# Gates.net
KiCad netlist of a schematic drawn in Altium Designer
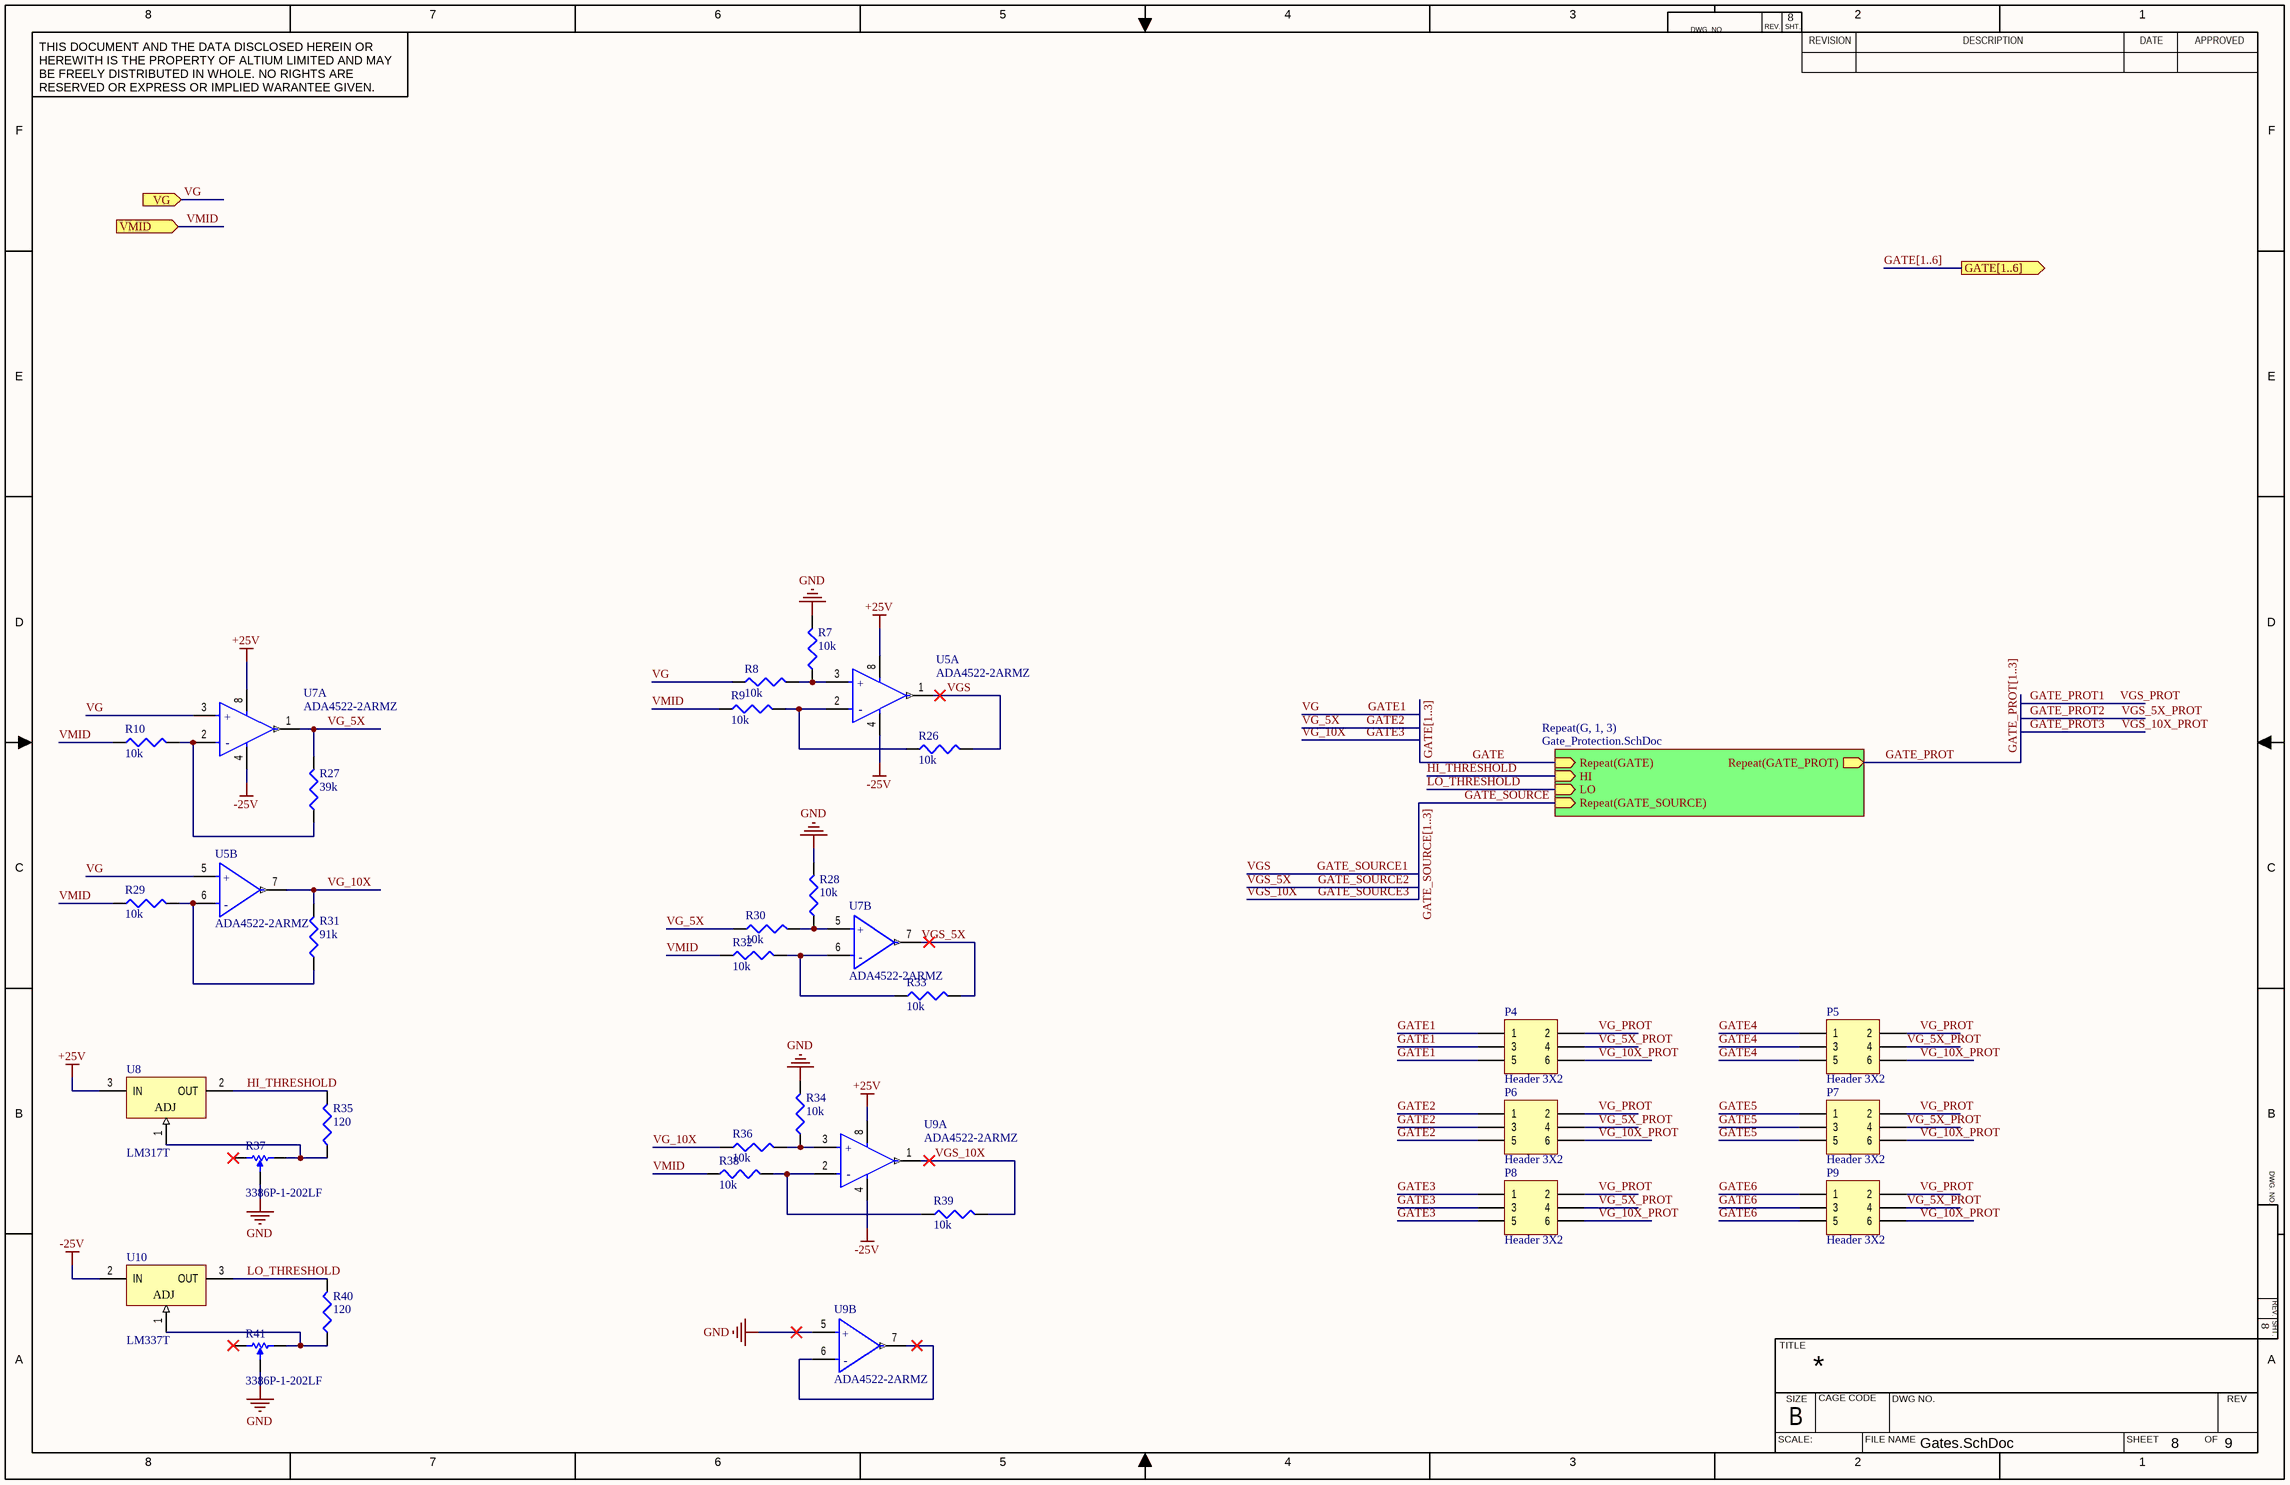
[diagram p0: Gates.SchDoc]

(export (version "E")
  (design (tool "Eeschema 10.0.6"))
  (components
    (comp (ref "P4")
      (value "Header 3X2")
      (footprint "HDR2X3")
      (description "Header, 3-Pin, Dual row")
      (fields (field (name "PUBLISHER") "Altium Limited"))
      (libsource (lib "Miscellaneous Connectors") (part "Header 3X2"))
    )
    (comp (ref "P5")
      (value "Header 3X2")
      (footprint "HDR2X3")
      (description "Header, 3-Pin, Dual row")
      (fields (field (name "PUBLISHER") "Altium Limited"))
      (libsource (lib "Miscellaneous Connectors") (part "Header 3X2"))
    )
    (comp (ref "P6")
      (value "Header 3X2")
      (footprint "HDR2X3")
      (description "Header, 3-Pin, Dual row")
      (fields (field (name "PUBLISHER") "Altium Limited"))
      (libsource (lib "Miscellaneous Connectors") (part "Header 3X2"))
    )
    (comp (ref "P7")
      (value "Header 3X2")
      (footprint "HDR2X3")
      (description "Header, 3-Pin, Dual row")
      (fields (field (name "PUBLISHER") "Altium Limited"))
      (libsource (lib "Miscellaneous Connectors") (part "Header 3X2"))
    )
    (comp (ref "P8")
      (value "Header 3X2")
      (footprint "HDR2X3")
      (description "Header, 3-Pin, Dual row")
      (fields (field (name "PUBLISHER") "Altium Limited"))
      (libsource (lib "Miscellaneous Connectors") (part "Header 3X2"))
    )
    (comp (ref "P9")
      (value "Header 3X2")
      (footprint "HDR2X3")
      (description "Header, 3-Pin, Dual row")
      (fields (field (name "PUBLISHER") "Altium Limited"))
      (libsource (lib "Miscellaneous Connectors") (part "Header 3X2"))
    )
    (comp (ref "R7")
      (value "10k")
      (footprint "J1-0603")
      (description "Resistor")
      (fields (field (name "PUBLISHER") "Altium Limited"))
      (libsource (lib "Miscellaneous Devices") (part "Res3"))
    )
    (comp (ref "R8")
      (value "10k")
      (footprint "J1-0603")
      (description "Resistor")
      (fields (field (name "PUBLISHER") "Altium Limited"))
      (libsource (lib "Miscellaneous Devices") (part "Res3"))
    )
    (comp (ref "R9")
      (value "10k")
      (footprint "J1-0603")
      (description "Resistor")
      (fields (field (name "PUBLISHER") "Altium Limited"))
      (libsource (lib "Miscellaneous Devices") (part "Res3"))
    )
    (comp (ref "R10")
      (value "10k")
      (footprint "J1-0603")
      (description "Resistor")
      (fields (field (name "PUBLISHER") "Altium Limited"))
      (libsource (lib "Miscellaneous Devices") (part "Res3"))
    )
    (comp (ref "R26")
      (value "10k")
      (footprint "J1-0603")
      (description "Resistor")
      (fields (field (name "PUBLISHER") "Altium Limited"))
      (libsource (lib "Miscellaneous Devices") (part "Res3"))
    )
    (comp (ref "R27")
      (value "39k")
      (footprint "J1-0603")
      (description "Resistor")
      (fields (field (name "PUBLISHER") "Altium Limited"))
      (libsource (lib "Miscellaneous Devices") (part "Res3"))
    )
    (comp (ref "R28")
      (value "10k")
      (footprint "J1-0603")
      (description "Resistor")
      (fields (field (name "PUBLISHER") "Altium Limited"))
      (libsource (lib "Miscellaneous Devices") (part "Res3"))
    )
    (comp (ref "R29")
      (value "10k")
      (footprint "J1-0603")
      (description "Resistor")
      (fields (field (name "PUBLISHER") "Altium Limited"))
      (libsource (lib "Miscellaneous Devices") (part "Res3"))
    )
    (comp (ref "R30")
      (value "10k")
      (footprint "J1-0603")
      (description "Resistor")
      (fields (field (name "PUBLISHER") "Altium Limited"))
      (libsource (lib "Miscellaneous Devices") (part "Res3"))
    )
    (comp (ref "R31")
      (value "91k")
      (footprint "J1-0603")
      (description "Resistor")
      (fields (field (name "PUBLISHER") "Altium Limited"))
      (libsource (lib "Miscellaneous Devices") (part "Res3"))
    )
    (comp (ref "R32")
      (value "10k")
      (footprint "J1-0603")
      (description "Resistor")
      (fields (field (name "PUBLISHER") "Altium Limited"))
      (libsource (lib "Miscellaneous Devices") (part "Res3"))
    )
    (comp (ref "R33")
      (value "10k")
      (footprint "J1-0603")
      (description "Resistor")
      (fields (field (name "PUBLISHER") "Altium Limited"))
      (libsource (lib "Miscellaneous Devices") (part "Res3"))
    )
    (comp (ref "R34")
      (value "10k")
      (footprint "J1-0603")
      (description "Resistor")
      (fields (field (name "PUBLISHER") "Altium Limited"))
      (libsource (lib "Miscellaneous Devices") (part "Res3"))
    )
    (comp (ref "R35")
      (value "120")
      (footprint "J1-0603")
      (description "Resistor")
      (fields (field (name "PUBLISHER") "Altium Limited"))
      (libsource (lib "Miscellaneous Devices") (part "Res3"))
    )
    (comp (ref "R36")
      (value "10k")
      (footprint "J1-0603")
      (description "Resistor")
      (fields (field (name "PUBLISHER") "Altium Limited"))
      (libsource (lib "Miscellaneous Devices") (part "Res3"))
    )
    (comp (ref "R37")
      (value "3386P-1-202LF")
      (footprint "BOUR-3386P")
      (fields (field (name "TOLERANCE") "10%") (field (name "MANUFACTURER") "Bourns"))
      (libsource (lib "Altium Content Vault") (part "RES-ADJ-3_A"))
    )
    (comp (ref "R38")
      (value "10k")
      (footprint "J1-0603")
      (description "Resistor")
      (fields (field (name "PUBLISHER") "Altium Limited"))
      (libsource (lib "Miscellaneous Devices") (part "Res3"))
    )
    (comp (ref "R39")
      (value "10k")
      (footprint "J1-0603")
      (description "Resistor")
      (fields (field (name "PUBLISHER") "Altium Limited"))
      (libsource (lib "Miscellaneous Devices") (part "Res3"))
    )
    (comp (ref "R40")
      (value "120")
      (footprint "J1-0603")
      (description "Resistor")
      (fields (field (name "PUBLISHER") "Altium Limited"))
      (libsource (lib "Miscellaneous Devices") (part "Res3"))
    )
    (comp (ref "R41")
      (value "3386P-1-202LF")
      (footprint "BOUR-3386P")
      (fields (field (name "TOLERANCE") "10%") (field (name "MANUFACTURER") "Bourns"))
      (libsource (lib "Altium Content Vault") (part "RES-ADJ-3_A"))
    )
    (comp (ref "U5")
      (value "ADA4522-2ARMZ")
      (footprint "FP-RM-8-IPC_C")
      (description "IC OPAMP ZERO-DRIFT 2 CIRC 8MSOP")
      (libsource (lib "Altium Content Vault") (part "e8c52d48d03680a0ba04c611cf3b55d"))
    )
    (comp (ref "U7")
      (value "ADA4522-2ARMZ")
      (footprint "FP-RM-8-IPC_C")
      (description "IC OPAMP ZERO-DRIFT 2 CIRC 8MSOP")
      (libsource (lib "Altium Content Vault") (part "e8c52d48d03680a0ba04c611cf3b55d"))
    )
    (comp (ref "U8")
      (value "LM317T")
      (footprint "TO-220")
      (description "1.5A, 1.2V to 37V Adjustable Voltage Regulator, 3-Pin TO-220")
      (libsource (lib "Altium Content Vault") (part "PM-REG-117-SIL3"))
    )
    (comp (ref "U9")
      (value "ADA4522-2ARMZ")
      (footprint "FP-RM-8-IPC_C")
      (description "IC OPAMP ZERO-DRIFT 2 CIRC 8MSOP")
      (libsource (lib "Altium Content Vault") (part "e8c52d48d03680a0ba04c611cf3b55d"))
    )
    (comp (ref "U10")
      (value "LM337T")
      (footprint "NDE0003A")
      (description "3-Terminal Adjustable Negative Regulator, 3-pin TO-220")
      (fields (field (name "MANUFACTURER") "Texas Instruments"))
      (libsource (lib "Altium Content Vault") (part "PM-REG-LM150ADJ-CY3"))
    )
  )
  (nets
    (net (code "1") (name "+25V") (class "Default")
      (node (ref "U5") (pin "8") (pinfunction "V+_8") (pintype "power_in"))
      (node (ref "U7") (pin "8") (pinfunction "V+_8") (pintype "power_in"))
      (node (ref "U8") (pin "3") (pinfunction "IN_3") (pintype "power_in"))
      (node (ref "U9") (pin "8") (pinfunction "V+_8") (pintype "power_in"))
    )
    (net (code "2") (name "-25V") (class "Default")
      (node (ref "U10") (pin "2") (pinfunction "IN_2") (pintype "power_in"))
      (node (ref "U5") (pin "4") (pinfunction "V-_4") (pintype "power_in"))
      (node (ref "U7") (pin "4") (pinfunction "V-_4") (pintype "power_in"))
      (node (ref "U9") (pin "4") (pinfunction "V-_4") (pintype "power_in"))
    )
    (net (code "4") (name "/GATE1") (class "Default")
      (node (ref "P4") (pin "1") (pinfunction "1_1") (pintype "passive"))
      (node (ref "P4") (pin "3") (pinfunction "3_3") (pintype "passive"))
      (node (ref "P4") (pin "5") (pinfunction "5_5") (pintype "passive"))
      (node (ref "R8") (pin "1") (pinfunction "1_1") (pintype "passive"))
      (node (ref "U5") (pin "5") (pinfunction "+IN_B_5") (pintype "tri_state"))
      (node (ref "U7") (pin "3") (pinfunction "+IN_A_3") (pintype "tri_state"))
    )
    (net (code "5") (name "/GATE2") (class "Default")
      (node (ref "P6") (pin "1") (pinfunction "1_1") (pintype "passive"))
      (node (ref "P6") (pin "3") (pinfunction "3_3") (pintype "passive"))
      (node (ref "P6") (pin "5") (pinfunction "5_5") (pintype "passive"))
      (node (ref "R27") (pin "2") (pinfunction "2_2") (pintype "passive"))
      (node (ref "R30") (pin "1") (pinfunction "1_1") (pintype "passive"))
      (node (ref "U7") (pin "1") (pinfunction "OUT_A_1") (pintype "output"))
    )
    (net (code "6") (name "/GATE3") (class "Default")
      (node (ref "P8") (pin "1") (pinfunction "1_1") (pintype "passive"))
      (node (ref "P8") (pin "3") (pinfunction "3_3") (pintype "passive"))
      (node (ref "P8") (pin "5") (pinfunction "5_5") (pintype "passive"))
      (node (ref "R31") (pin "2") (pinfunction "2_2") (pintype "passive"))
      (node (ref "R36") (pin "1") (pinfunction "1_1") (pintype "passive"))
      (node (ref "U5") (pin "7") (pinfunction "OUT_B_7") (pintype "output"))
    )
    (net (code "7") (name "/GATE4") (class "Default")
      (node (ref "P5") (pin "1") (pinfunction "1_1") (pintype "passive"))
      (node (ref "P5") (pin "3") (pinfunction "3_3") (pintype "passive"))
      (node (ref "P5") (pin "5") (pinfunction "5_5") (pintype "passive"))
    )
    (net (code "8") (name "/GATE5") (class "Default")
      (node (ref "P7") (pin "1") (pinfunction "1_1") (pintype "passive"))
      (node (ref "P7") (pin "3") (pinfunction "3_3") (pintype "passive"))
      (node (ref "P7") (pin "5") (pinfunction "5_5") (pintype "passive"))
    )
    (net (code "9") (name "/GATE6") (class "Default")
      (node (ref "P9") (pin "1") (pinfunction "1_1") (pintype "passive"))
      (node (ref "P9") (pin "3") (pinfunction "3_3") (pintype "passive"))
      (node (ref "P9") (pin "5") (pinfunction "5_5") (pintype "passive"))
    )
    (net (code "18") (name "/GATE_SOURCE1") (class "Default")
      (node (ref "R26") (pin "2") (pinfunction "2_2") (pintype "passive"))
      (node (ref "U5") (pin "1") (pinfunction "OUT_A_1") (pintype "output"))
    )
    (net (code "19") (name "/GATE_SOURCE2") (class "Default")
      (node (ref "R33") (pin "2") (pinfunction "2_2") (pintype "passive"))
      (node (ref "U7") (pin "7") (pinfunction "OUT_B_7") (pintype "output"))
    )
    (net (code "20") (name "/GATE_SOURCE3") (class "Default")
      (node (ref "R39") (pin "2") (pinfunction "2_2") (pintype "passive"))
      (node (ref "U9") (pin "1") (pinfunction "OUT_A_1") (pintype "output"))
    )
    (net (code "22") (name "/HI_THRESHOLD") (class "Default")
      (node (ref "R35") (pin "2") (pinfunction "2_2") (pintype "passive"))
      (node (ref "U8") (pin "2") (pinfunction "OUT_2") (pintype "power_in"))
    )
    (net (code "23") (name "/LO_THRESHOLD") (class "Default")
      (node (ref "R40") (pin "2") (pinfunction "2_2") (pintype "passive"))
      (node (ref "U10") (pin "3") (pinfunction "OUT_3") (pintype "power_in"))
    )
    (net (code "24") (name "/VG_5X_PROT") (class "Default")
      (node (ref "P4") (pin "4") (pinfunction "4_4") (pintype "passive"))
      (node (ref "P5") (pin "4") (pinfunction "4_4") (pintype "passive"))
      (node (ref "P6") (pin "4") (pinfunction "4_4") (pintype "passive"))
      (node (ref "P7") (pin "4") (pinfunction "4_4") (pintype "passive"))
      (node (ref "P8") (pin "4") (pinfunction "4_4") (pintype "passive"))
      (node (ref "P9") (pin "4") (pinfunction "4_4") (pintype "passive"))
    )
    (net (code "25") (name "/VG_10X_PROT") (class "Default")
      (node (ref "P4") (pin "6") (pinfunction "6_6") (pintype "passive"))
      (node (ref "P5") (pin "6") (pinfunction "6_6") (pintype "passive"))
      (node (ref "P6") (pin "6") (pinfunction "6_6") (pintype "passive"))
      (node (ref "P7") (pin "6") (pinfunction "6_6") (pintype "passive"))
      (node (ref "P8") (pin "6") (pinfunction "6_6") (pintype "passive"))
      (node (ref "P9") (pin "6") (pinfunction "6_6") (pintype "passive"))
    )
    (net (code "26") (name "/VG_PROT") (class "Default")
      (node (ref "P4") (pin "2") (pinfunction "2_2") (pintype "passive"))
      (node (ref "P5") (pin "2") (pinfunction "2_2") (pintype "passive"))
      (node (ref "P6") (pin "2") (pinfunction "2_2") (pintype "passive"))
      (node (ref "P7") (pin "2") (pinfunction "2_2") (pintype "passive"))
      (node (ref "P8") (pin "2") (pinfunction "2_2") (pintype "passive"))
      (node (ref "P9") (pin "2") (pinfunction "2_2") (pintype "passive"))
    )
    (net (code "27") (name "/VMID") (class "Default")
      (node (ref "R10") (pin "1") (pinfunction "1_1") (pintype "passive"))
      (node (ref "R29") (pin "1") (pinfunction "1_1") (pintype "passive"))
      (node (ref "R32") (pin "1") (pinfunction "1_1") (pintype "passive"))
      (node (ref "R38") (pin "1") (pinfunction "1_1") (pintype "passive"))
      (node (ref "R9") (pin "1") (pinfunction "1_1") (pintype "passive"))
    )
    (net (code "28") (name "GND") (class "Default")
      (node (ref "R28") (pin "2") (pinfunction "2_2") (pintype "passive"))
      (node (ref "R34") (pin "2") (pinfunction "2_2") (pintype "passive"))
      (node (ref "R37") (pin "2") (pinfunction "2_2") (pintype "passive"))
      (node (ref "R41") (pin "2") (pinfunction "2_2") (pintype "passive"))
      (node (ref "R7") (pin "2") (pinfunction "2_2") (pintype "passive"))
      (node (ref "U9") (pin "5") (pinfunction "+IN_B_5") (pintype "tri_state"))
    )
    (net (code "29") (name "Net-(U5A-+IN_A)") (class "Default")
      (node (ref "R7") (pin "1") (pinfunction "1_1") (pintype "passive"))
      (node (ref "R8") (pin "2") (pinfunction "2_2") (pintype "passive"))
      (node (ref "U5") (pin "3") (pinfunction "+IN_A_3") (pintype "tri_state"))
    )
    (net (code "30") (name "Net-(U5A--IN_A)") (class "Default")
      (node (ref "R26") (pin "1") (pinfunction "1_1") (pintype "passive"))
      (node (ref "R9") (pin "2") (pinfunction "2_2") (pintype "passive"))
      (node (ref "U5") (pin "2") (pinfunction "-IN_A_2") (pintype "tri_state"))
    )
    (net (code "31") (name "Net-(U5B--IN_B)") (class "Default")
      (node (ref "R29") (pin "2") (pinfunction "2_2") (pintype "passive"))
      (node (ref "R31") (pin "1") (pinfunction "1_1") (pintype "passive"))
      (node (ref "U5") (pin "6") (pinfunction "-IN_B_6") (pintype "tri_state"))
    )
    (net (code "32") (name "Net-(U7A--IN_A)") (class "Default")
      (node (ref "R10") (pin "2") (pinfunction "2_2") (pintype "passive"))
      (node (ref "R27") (pin "1") (pinfunction "1_1") (pintype "passive"))
      (node (ref "U7") (pin "2") (pinfunction "-IN_A_2") (pintype "tri_state"))
    )
    (net (code "33") (name "Net-(U7B-+IN_B)") (class "Default")
      (node (ref "R28") (pin "1") (pinfunction "1_1") (pintype "passive"))
      (node (ref "R30") (pin "2") (pinfunction "2_2") (pintype "passive"))
      (node (ref "U7") (pin "5") (pinfunction "+IN_B_5") (pintype "tri_state"))
    )
    (net (code "34") (name "Net-(U7B--IN_B)") (class "Default")
      (node (ref "R32") (pin "2") (pinfunction "2_2") (pintype "passive"))
      (node (ref "R33") (pin "1") (pinfunction "1_1") (pintype "passive"))
      (node (ref "U7") (pin "6") (pinfunction "-IN_B_6") (pintype "tri_state"))
    )
    (net (code "35") (name "Net-(U8-ADJ)") (class "Default")
      (node (ref "R35") (pin "1") (pinfunction "1_1") (pintype "passive"))
      (node (ref "R37") (pin "3") (pinfunction "3_3") (pintype "passive"))
      (node (ref "U8") (pin "1") (pinfunction "ADJ_1") (pintype "input"))
    )
    (net (code "36") (name "Net-(U9A-+IN_A)") (class "Default")
      (node (ref "R34") (pin "1") (pinfunction "1_1") (pintype "passive"))
      (node (ref "R36") (pin "2") (pinfunction "2_2") (pintype "passive"))
      (node (ref "U9") (pin "3") (pinfunction "+IN_A_3") (pintype "tri_state"))
    )
    (net (code "37") (name "Net-(U9A--IN_A)") (class "Default")
      (node (ref "R38") (pin "2") (pinfunction "2_2") (pintype "passive"))
      (node (ref "R39") (pin "1") (pinfunction "1_1") (pintype "passive"))
      (node (ref "U9") (pin "2") (pinfunction "-IN_A_2") (pintype "tri_state"))
    )
    (net (code "38") (name "Net-(U9B--IN_B)") (class "Default")
      (node (ref "U9") (pin "6") (pinfunction "-IN_B_6") (pintype "tri_state"))
      (node (ref "U9") (pin "7") (pinfunction "OUT_B_7") (pintype "output"))
    )
    (net (code "39") (name "Net-(U10-ADJ)") (class "Default")
      (node (ref "R40") (pin "1") (pinfunction "1_1") (pintype "passive"))
      (node (ref "R41") (pin "3") (pinfunction "3_3") (pintype "passive"))
      (node (ref "U10") (pin "1") (pinfunction "ADJ_1") (pintype "input"))
    )
    (net (code "40") (name "unconnected-(R37-Pad1)") (class "Default")
      (node (ref "R37") (pin "1") (pinfunction "1_1") (pintype "passive+no_connect"))
    )
    (net (code "41") (name "unconnected-(R41-Pad1)") (class "Default")
      (node (ref "R41") (pin "1") (pinfunction "1_1") (pintype "passive+no_connect"))
    )
  )
)
